# display.net
KiCad netlist of a schematic drawn in Altium Designer
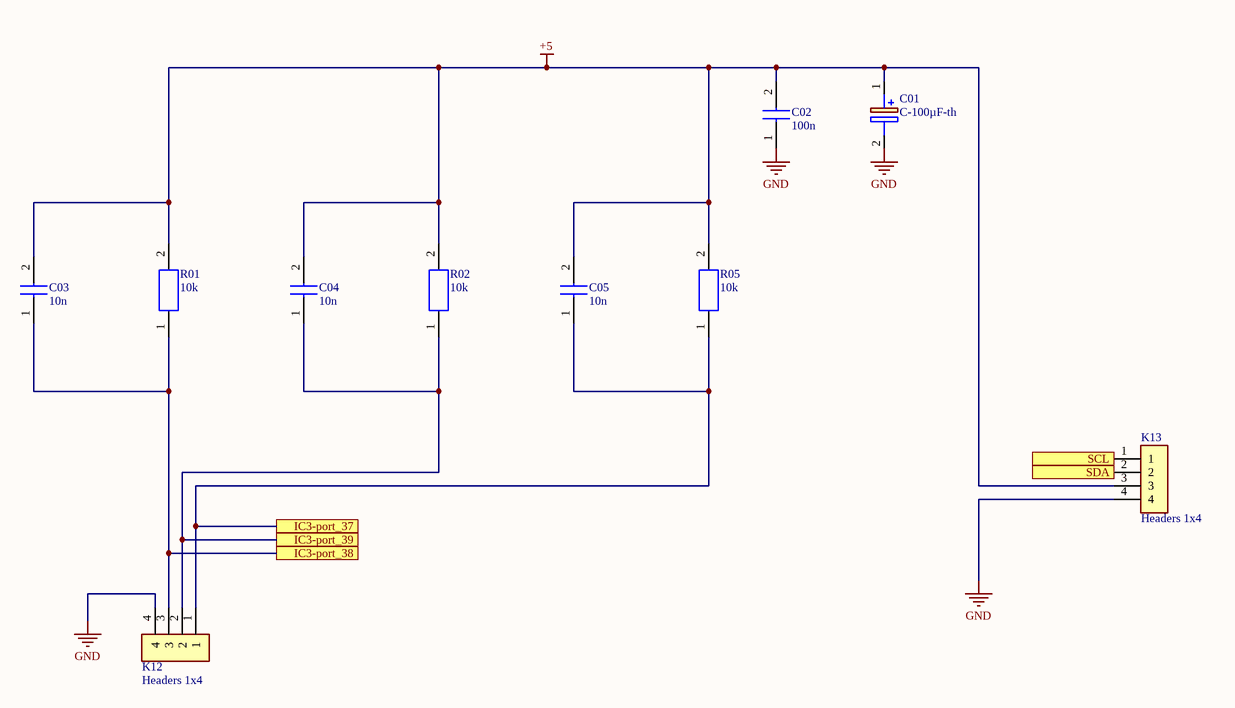
[diagram p0: display.SchDoc]

(export (version "E")
  (design (tool "Eeschema 10.0.6"))
  (components
    (comp (ref "C01")
      (value "C-100µF-th")
      (footprint "C-100µF-th")
      (description "Capacitor Polarised")
      (fields (field (name "MANUFACTURER_PART_NUMBER") "ESK107M050AG3EA"))
      (libsource (lib "project-2022") (part "C-100µF-th"))
    )
    (comp (ref "C02")
      (value "100n")
      (footprint "C-0805-smd")
      (description "Capacitor")
      (fields (field (name "MANUFACTURER_PART_NUMBER") "C0805C301G5GACTU"))
      (libsource (lib "project-2022") (part "C-0805-smd"))
    )
    (comp (ref "C03")
      (value "10n")
      (footprint "C-0805-smd")
      (description "Capacitor")
      (fields (field (name "MANUFACTURER_PART_NUMBER") "C0805C301G5GACTU"))
      (libsource (lib "project-2022") (part "C-0805-smd"))
    )
    (comp (ref "C04")
      (value "10n")
      (footprint "C-0805-smd")
      (description "Capacitor")
      (fields (field (name "MANUFACTURER_PART_NUMBER") "C0805C301G5GACTU"))
      (libsource (lib "project-2022") (part "C-0805-smd"))
    )
    (comp (ref "C05")
      (value "10n")
      (footprint "C-0805-smd")
      (description "Capacitor")
      (fields (field (name "MANUFACTURER_PART_NUMBER") "C0805C301G5GACTU"))
      (libsource (lib "project-2022") (part "C-0805-smd"))
    )
    (comp (ref "K12")
      (value "Headers 1x4")
      (footprint "Headers 1x4")
      (description "Connector")
      (fields (field (name "MANUFACTURER_PART_NUMBER") "2-826646-0"))
      (libsource (lib "project-2022") (part "Headers 1x4"))
    )
    (comp (ref "K13")
      (value "Headers 1x4")
      (footprint "Headers 1x4")
      (description "Connector")
      (fields (field (name "MANUFACTURER_PART_NUMBER") "2-826646-0"))
      (libsource (lib "") (part "Headers 1x4_1"))
    )
    (comp (ref "R01")
      (value "10k")
      (footprint "R-0805")
      (description "Resistor")
      (fields (field (name "MANUFACTURER_PART_NUMBER") "TNPU0805500RAZEN00"))
      (libsource (lib "project-2022") (part "R-0805"))
    )
    (comp (ref "R02")
      (value "10k")
      (footprint "R-0805")
      (description "Resistor")
      (fields (field (name "MANUFACTURER_PART_NUMBER") "TNPU0805500RAZEN00"))
      (libsource (lib "project-2022") (part "R-0805"))
    )
    (comp (ref "R05")
      (value "10k")
      (footprint "R-0805")
      (description "Resistor")
      (fields (field (name "MANUFACTURER_PART_NUMBER") "TNPU0805500RAZEN00"))
      (libsource (lib "project-2022") (part "R-0805"))
    )
  )
  (nets
    (net (code "1") (name "+5") (class "Default")
      (node (ref "C01") (pin "1") (pinfunction "+_1") (pintype "passive"))
      (node (ref "C02") (pin "2") (pinfunction "2_2") (pintype "passive"))
      (node (ref "C03") (pin "2") (pinfunction "2_2") (pintype "passive"))
      (node (ref "C04") (pin "2") (pinfunction "2_2") (pintype "passive"))
      (node (ref "C05") (pin "2") (pinfunction "2_2") (pintype "passive"))
      (node (ref "K13") (pin "3") (pinfunction "3_3") (pintype "passive"))
      (node (ref "R01") (pin "2") (pinfunction "2_2") (pintype "passive"))
      (node (ref "R02") (pin "2") (pinfunction "2_2") (pintype "passive"))
      (node (ref "R05") (pin "2") (pinfunction "2_2") (pintype "passive"))
    )
    (net (code "2") (name "/IC3-port_37") (class "Default")
      (node (ref "C05") (pin "1") (pinfunction "1_1") (pintype "passive"))
      (node (ref "K12") (pin "1") (pinfunction "1_1") (pintype "passive"))
      (node (ref "R05") (pin "1") (pinfunction "1_1") (pintype "passive"))
    )
    (net (code "3") (name "/IC3-port_38") (class "Default")
      (node (ref "C03") (pin "1") (pinfunction "1_1") (pintype "passive"))
      (node (ref "K12") (pin "3") (pinfunction "3_3") (pintype "passive"))
      (node (ref "R01") (pin "1") (pinfunction "1_1") (pintype "passive"))
    )
    (net (code "4") (name "/IC3-port_39") (class "Default")
      (node (ref "C04") (pin "1") (pinfunction "1_1") (pintype "passive"))
      (node (ref "K12") (pin "2") (pinfunction "2_2") (pintype "passive"))
      (node (ref "R02") (pin "1") (pinfunction "1_1") (pintype "passive"))
    )
    (net (code "5") (name "/SCL") (class "Default")
      (node (ref "K13") (pin "1") (pinfunction "1_1") (pintype "passive"))
    )
    (net (code "6") (name "/SDA") (class "Default")
      (node (ref "K13") (pin "2") (pinfunction "2_2") (pintype "passive"))
    )
    (net (code "7") (name "GND") (class "Default")
      (node (ref "C01") (pin "2") (pinfunction "-_2") (pintype "passive"))
      (node (ref "C02") (pin "1") (pinfunction "1_1") (pintype "passive"))
      (node (ref "K12") (pin "4") (pinfunction "4_4") (pintype "passive"))
      (node (ref "K13") (pin "4") (pinfunction "4_4") (pintype "passive"))
    )
  )
)
